# PowerSupply.net
KiCad netlist of a schematic drawn in Altium Designer
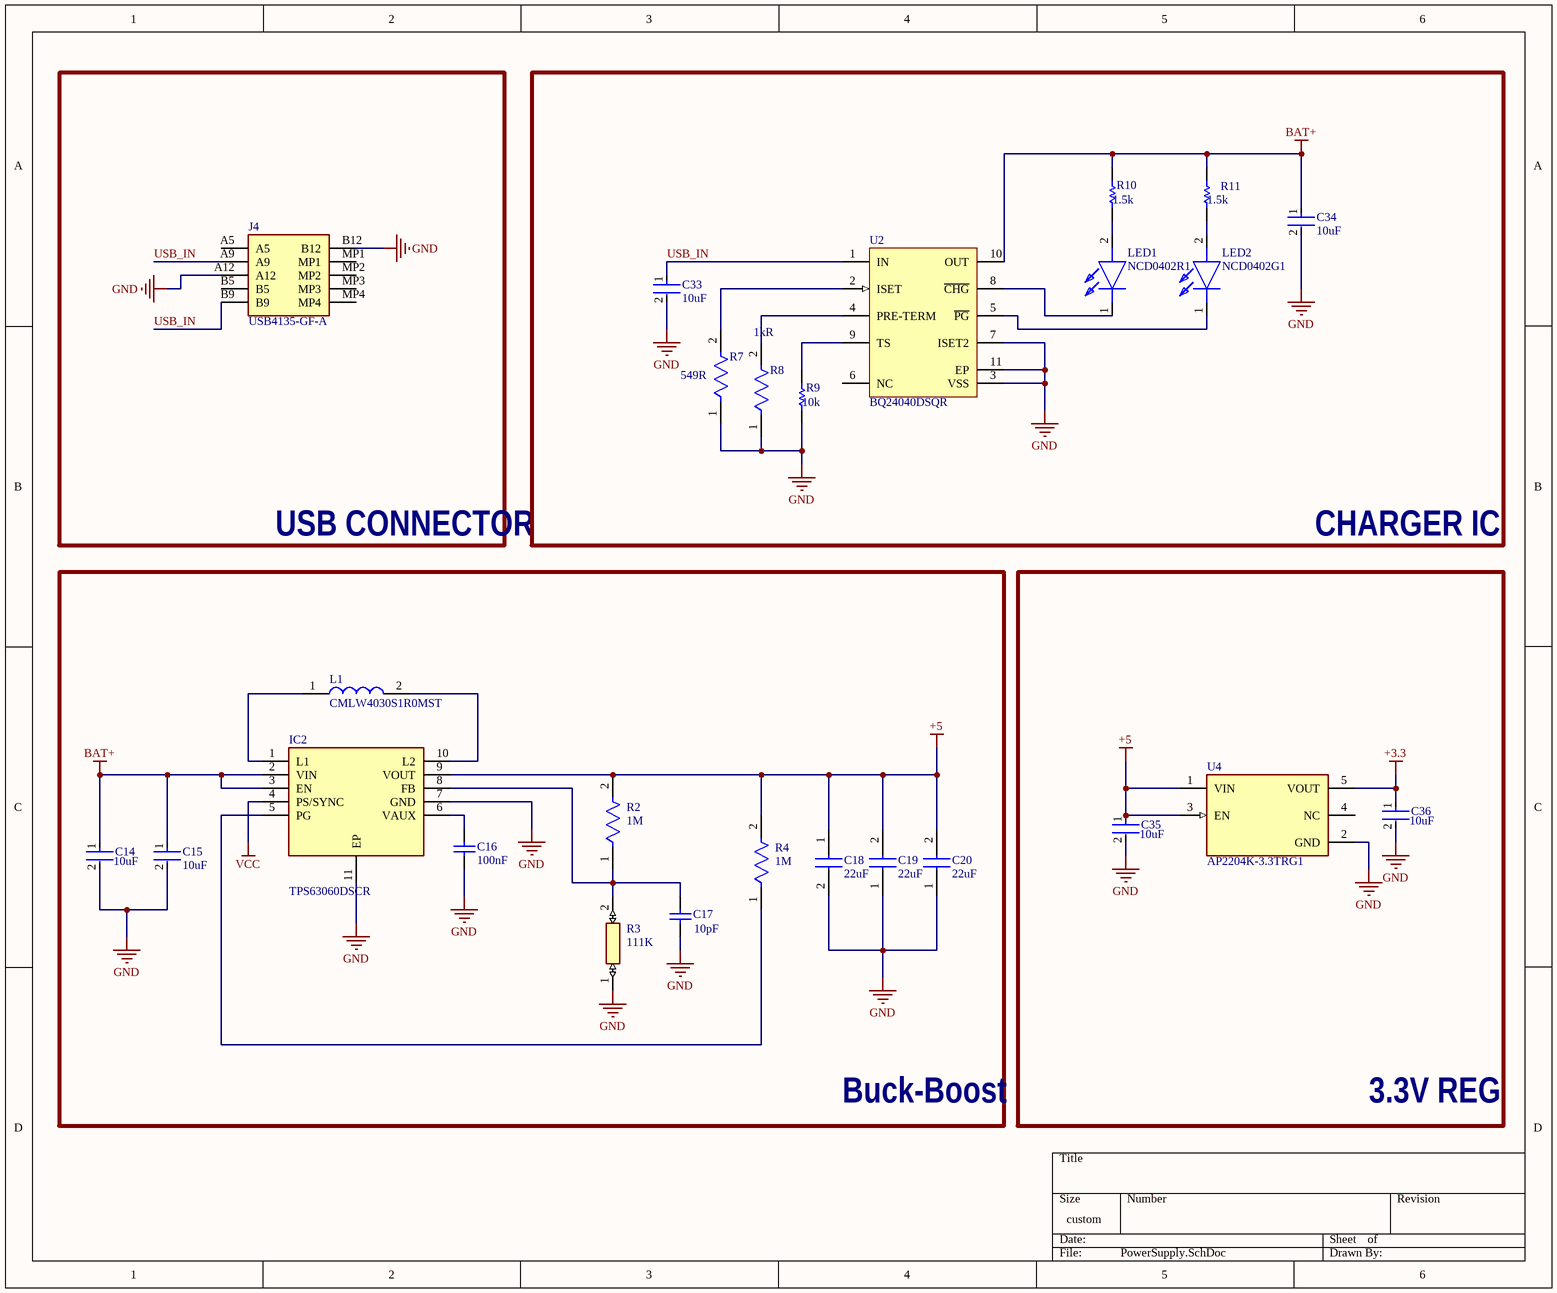
[diagram p0: PowerSupply.SchDoc]

(export (version "E")
  (design (tool "Eeschema 10.0.6"))
  (components
    (comp (ref "C14")
      (value "CL05A106MP5NUNC")
      (footprint "FP-CL05A106MP5NUNC-MFG")
      (description "CAP CER 10UF 10V X5R 0402")
      (fields
        (field (name "OCTOPART") "https://octopart.com/cl05a106mp5nunc-samsung-22457395")
        (field (name "TOLERANCE") "20%")
        (field (name "CAPACITANCE") "10uF")
      )
      (libsource (lib "Altium Content Vault") (part "b4654b650e69147ec39a6b967a45e02"))
    )
    (comp (ref "C15")
      (value "CL05A106MP5NUNC")
      (footprint "FP-CL05A106MP5NUNC-MFG")
      (description "CAP CER 10UF 10V X5R 0402")
      (fields
        (field (name "OCTOPART") "https://octopart.com/cl05a106mp5nunc-samsung-22457395")
        (field (name "TOLERANCE") "20%")
        (field (name "CAPACITANCE") "10uF")
      )
      (libsource (lib "Altium Content Vault") (part "b4654b650e69147ec39a6b967a45e02"))
    )
    (comp (ref "C16")
      (value "CL05B104KO5NNNC")
      (footprint "CAPC1050X55X23ML05T13")
      (description "Chip Capacitor, 100 nF, +/- 10%, 16 V, -55 to 125 degC, 0402 (1005 Metric), RoHS, Tape and Reel")
      (fields (field (name "MANUFACTURER") "Samsung Electro-Mechanics") (field (name "CAPACITANCE") "100nF"))
      (libsource (lib "Altium Content Vault") (part "CAP-NP-2"))
    )
    (comp (ref "C17")
      (value "CC0402JRNPO9BN100")
      (footprint "CAPC1005X55X25ML05T05")
      (description "Chip Capacitor, 10 pF, +/- 5%, 50 V, -55 to 125 degC, 0402 (1005 Metric), RoHS, Tape and Reel")
      (fields
        (field (name "TOLERANCE") "5%")
        (field (name "MANUFACTURER") "Yageo")
        (field (name "CAPACITANCE") "10pF")
      )
      (libsource (lib "Altium Content Vault") (part "CAP-NP-2"))
    )
    (comp (ref "C18")
      (value "22uF")
      (footprint "SamacSys:CAPC1608X105N")
      (description "Capacitor")
      (fields
        (field (name "MANUFACTURER_PART_NUMBER") "CL10A226MP8NUNE")
        (field (name "MOUSER PART NUMBER") "187-CL10A226MP8NUNE")
      )
      (libsource (lib "*") (part "CL10A226MP8NUNE"))
    )
    (comp (ref "C19")
      (value "22uF")
      (footprint "SamacSys:CAPC1608X105N")
      (description "Capacitor")
      (fields
        (field (name "MANUFACTURER_PART_NUMBER") "CL10A226MP8NUNE")
        (field (name "MOUSER PART NUMBER") "187-CL10A226MP8NUNE")
      )
      (libsource (lib "*") (part "CL10A226MP8NUNE"))
    )
    (comp (ref "C20")
      (value "22uF")
      (footprint "SamacSys:CAPC1608X105N")
      (description "Capacitor")
      (fields
        (field (name "MANUFACTURER_PART_NUMBER") "CL10A226MP8NUNE")
        (field (name "MOUSER PART NUMBER") "187-CL10A226MP8NUNE")
      )
      (libsource (lib "*") (part "CL10A226MP8NUNE"))
    )
    (comp (ref "C33")
      (value "CL05A106MP5NUNC")
      (footprint "FP-CL05A106MP5NUNC-MFG")
      (description "CAP CER 10UF 10V X5R 0402")
      (fields
        (field (name "OCTOPART") "https://octopart.com/cl05a106mp5nunc-samsung-22457395")
        (field (name "TOLERANCE") "20%")
        (field (name "CAPACITANCE") "10uF")
      )
      (libsource (lib "Altium Content Vault") (part "b4654b650e69147ec39a6b967a45e02"))
    )
    (comp (ref "C34")
      (value "CL05A106MP5NUNC")
      (footprint "FP-CL05A106MP5NUNC-MFG")
      (description "CAP CER 10UF 10V X5R 0402")
      (fields
        (field (name "OCTOPART") "https://octopart.com/cl05a106mp5nunc-samsung-22457395")
        (field (name "TOLERANCE") "20%")
        (field (name "CAPACITANCE") "10uF")
      )
      (libsource (lib "Altium Content Vault") (part "b4654b650e69147ec39a6b967a45e02"))
    )
    (comp (ref "C35")
      (value "CL05A106MP5NUNC")
      (footprint "FP-CL05A106MP5NUNC-MFG")
      (description "CAP CER 10UF 10V X5R 0402")
      (fields
        (field (name "OCTOPART") "https://octopart.com/cl05a106mp5nunc-samsung-22457395")
        (field (name "TOLERANCE") "20%")
        (field (name "CAPACITANCE") "10uF")
      )
      (libsource (lib "Altium Content Vault") (part "b4654b650e69147ec39a6b967a45e02"))
    )
    (comp (ref "C36")
      (value "CL05A106MP5NUNC")
      (footprint "FP-CL05A106MP5NUNC-MFG")
      (description "CAP CER 10UF 10V X5R 0402")
      (fields
        (field (name "OCTOPART") "https://octopart.com/cl05a106mp5nunc-samsung-22457395")
        (field (name "TOLERANCE") "20%")
        (field (name "CAPACITANCE") "10uF")
      )
      (libsource (lib "Altium Content Vault") (part "b4654b650e69147ec39a6b967a45e02"))
    )
    (comp (ref "IC2")
      (value "TPS63060DSCR")
      (footprint "SamacSys:SON50P300X300X80-11N-D")
      (description "Integrated Circuit")
      (fields (field (name "MOUSER PART NUMBER") "595-TPS63060DSCR"))
      (libsource (lib "*") (part "TPS63060DSCR"))
    )
    (comp (ref "J4")
      (value "USB4135-GF-A")
      (footprint "SamacSys:USB4135GFA")
      (description "Connector")
      (fields (field (name "MOUSER PART NUMBER") "640-USB4135-GF-A"))
      (libsource (lib "SamacSys") (part "USB4135-GF-A"))
    )
    (comp (ref "L1")
      (value "CMLW4030S1R0MST")
      (footprint "SamacSys:LSDPD4040WKT4R7MML")
      (description "Inductor")
      (fields
        (field (name "MANUFACTURER_PART_NUMBER") "LSDPD4040WKT4R7MML")
        (field (name "MOUSER PART NUMBER") "963-LSDPD4040WKT4R7M")
      )
      (libsource (lib "*") (part "LSDPD4040WKT4R7MML"))
    )
    (comp (ref "LED1")
      (value "NCD0402R1")
      (footprint "SamacSys:NCD0402R1")
      (description "LED")
      (libsource (lib "*") (part "NCD0402R1"))
    )
    (comp (ref "LED2")
      (value "NCD0402G1")
      (footprint "SamacSys:NCD0402R1")
      (description "LED  NCD0402G1")
      (fields (field (name "MANUFACTURER_PART_NUMBER") "NCD0402R1"))
      (libsource (lib "*") (part "NCD0402R1"))
    )
    (comp (ref "R2")
      (value "1M")
      (footprint "FP-AC0402-IPC_C")
      (description "RES 1MΩ ±0.5% 0.063W 0402")
      (fields (field (name "Comment") "AC0402DR-071ML"))
      (libsource (lib "Altium Content Vault") (part "1029c3af85768c4190bb7ad29bc67b5"))
    )
    (comp (ref "R3")
      (value "111K")
      (footprint "SamacSys:RESC2012X60N")
      (description "Resistor")
      (fields
        (field (name "MANUFACTURER_PART_NUMBER") "RT0805BRD07111KL")
        (field (name "MOUSER PART NUMBER") "603-RT0805BRD07111KL")
      )
      (libsource (lib "*") (part "RT0805BRD07111KL"))
    )
    (comp (ref "R4")
      (value "1M")
      (footprint "FP-AC0402-IPC_C")
      (description "RES 1MΩ ±0.5% 0.063W 0402")
      (fields (field (name "Comment") "AC0402DR-071ML"))
      (libsource (lib "Altium Content Vault") (part "1029c3af85768c4190bb7ad29bc67b5"))
    )
    (comp (ref "R7")
      (value "AC0402FR-07549RL")
      (footprint "FP-AC0402-IPC_B")
      (description "RES 549Ω ±1% 0.063W 0402")
      (fields (field (name "TOLERANCE") "1%") (field (name "RESISTANCE") "549R"))
      (libsource (lib "Altium Content Vault") (part "1029c3af85768c4190bb7ad29bc67b5"))
    )
    (comp (ref "R8")
      (value "RC0402FR-071KL")
      (footprint "FP-RC0402-0_4-IPC_A")
      (description "RES 1K OHM 1% 1/16W 0402")
      (fields (field (name "TOLERANCE") "1%") (field (name "RESISTANCE") "1kR"))
      (libsource (lib "Altium Content Vault") (part "1029c3af85768c4190bb7ad29bc67b5"))
    )
    (comp (ref "R9")
      (value "10k")
      (footprint "RESC1005X40X25ML05T10")
      (fields (field (name "PART NUMBER") "RC0402FR-0710KL") (field (name "MANUFACTURER") "Yageo / Phycomp"))
      (libsource (lib "Altium Content Vault") (part "RES"))
    )
    (comp (ref "R10")
      (value "1.5k")
      (footprint "RESC1005X40X25ML05T10")
      (fields (field (name "MANUFACTURER") "Yageo / Phycomp") (field (name "PART NUMBER") "RC0402FR-071K5L"))
      (libsource (lib "Altium Content Vault") (part "RES"))
    )
    (comp (ref "R11")
      (value "1.5k")
      (footprint "RESC1005X40X25ML05T10")
      (fields (field (name "MANUFACTURER") "Yageo / Phycomp") (field (name "PART NUMBER") "RC0402FR-071K5L"))
      (libsource (lib "Altium Content Vault") (part "RES"))
    )
    (comp (ref "U2")
      (value "BQ24040DSQR")
      (footprint "DSQ0010A_V")
      (fields (field (name "MANUFACTURER") "Texas Instruments"))
      (libsource (lib "Altium Content Vault") (part "TI-BQ24040DSQ10-1500X900TP"))
    )
    (comp (ref "U4")
      (value "AP2204K-3.3TRG1")
      (footprint "FP-SOT25-IPC_C")
      (description "IC REG LINEAR 3.3V 150MA SOT23-5")
      (libsource (lib "Altium Content Vault") (part "038a824adfd04a965d73cdd9fb88cf2"))
    )
  )
  (nets
    (net (code "1") (name "+3.3") (class "Default")
      (node (ref "C36") (pin "1") (pinfunction "1_1") (pintype "passive"))
      (node (ref "U4") (pin "5") (pinfunction "VOUT_5") (pintype "power_in"))
    )
    (net (code "2") (name "+5") (class "Default")
      (node (ref "C18") (pin "1") (pinfunction "1_1") (pintype "passive"))
      (node (ref "C19") (pin "2") (pinfunction "2_2") (pintype "passive"))
      (node (ref "C20") (pin "2") (pinfunction "2_2") (pintype "passive"))
      (node (ref "C35") (pin "1") (pinfunction "1_1") (pintype "passive"))
      (node (ref "IC2") (pin "9") (pinfunction "VOUT_9") (pintype "passive"))
      (node (ref "R2") (pin "2") (pinfunction "2_2") (pintype "passive"))
      (node (ref "R4") (pin "2") (pinfunction "2_2") (pintype "passive"))
      (node (ref "U4") (pin "1") (pinfunction "VIN_1") (pintype "power_in"))
      (node (ref "U4") (pin "3") (pinfunction "EN_3") (pintype "input"))
    )
    (net (code "3") (name "/USB_IN") (class "Default")
      (node (ref "C33") (pin "1") (pinfunction "1_1") (pintype "passive"))
      (node (ref "J4") (pin "A9") (pinfunction "A9_A9") (pintype "passive"))
      (node (ref "J4") (pin "B9") (pinfunction "B9_B9") (pintype "passive"))
      (node (ref "U2") (pin "1") (pinfunction "IN_1") (pintype "power_in"))
    )
    (net (code "4") (name "BAT+") (class "Default")
      (node (ref "C14") (pin "1") (pinfunction "1_1") (pintype "passive"))
      (node (ref "C15") (pin "1") (pinfunction "1_1") (pintype "passive"))
      (node (ref "C34") (pin "1") (pinfunction "1_1") (pintype "passive"))
      (node (ref "IC2") (pin "2") (pinfunction "VIN_2") (pintype "passive"))
      (node (ref "IC2") (pin "3") (pinfunction "EN_3") (pintype "passive"))
      (node (ref "R10") (pin "2") (pinfunction "2_2") (pintype "passive"))
      (node (ref "R11") (pin "2") (pinfunction "2_2") (pintype "passive"))
      (node (ref "U2") (pin "10") (pinfunction "OUT_10") (pintype "power_in"))
    )
    (net (code "5") (name "GND") (class "Default")
      (node (ref "C14") (pin "2") (pinfunction "2_2") (pintype "passive"))
      (node (ref "C15") (pin "2") (pinfunction "2_2") (pintype "passive"))
      (node (ref "C16") (pin "1") (pinfunction "1_1") (pintype "passive"))
      (node (ref "C17") (pin "1") (pinfunction "1_1") (pintype "passive"))
      (node (ref "C18") (pin "2") (pinfunction "2_2") (pintype "passive"))
      (node (ref "C19") (pin "1") (pinfunction "1_1") (pintype "passive"))
      (node (ref "C20") (pin "1") (pinfunction "1_1") (pintype "passive"))
      (node (ref "C33") (pin "2") (pinfunction "2_2") (pintype "passive"))
      (node (ref "C34") (pin "2") (pinfunction "2_2") (pintype "passive"))
      (node (ref "C35") (pin "2") (pinfunction "2_2") (pintype "passive"))
      (node (ref "C36") (pin "2") (pinfunction "2_2") (pintype "passive"))
      (node (ref "IC2") (pin "11") (pinfunction "EP_11") (pintype "passive"))
      (node (ref "IC2") (pin "7") (pinfunction "GND_7") (pintype "passive"))
      (node (ref "J4") (pin "A12") (pinfunction "A12_A12") (pintype "passive"))
      (node (ref "J4") (pin "B12") (pinfunction "B12_B12") (pintype "passive"))
      (node (ref "R3") (pin "1") (pinfunction "1_1") (pintype "bidirectional"))
      (node (ref "R7") (pin "1") (pinfunction "1_1") (pintype "passive"))
      (node (ref "R8") (pin "1") (pinfunction "1_1") (pintype "passive"))
      (node (ref "R9") (pin "1") (pinfunction "1_1") (pintype "passive"))
      (node (ref "U2") (pin "11") (pinfunction "EP_11") (pintype "power_in"))
      (node (ref "U2") (pin "3") (pinfunction "VSS_3") (pintype "power_in"))
      (node (ref "U2") (pin "7") (pinfunction "ISET2_7") (pintype "passive"))
      (node (ref "U4") (pin "2") (pinfunction "GND_2") (pintype "power_in"))
    )
    (net (code "6") (name "Net-(IC2-FB)") (class "Default")
      (node (ref "C17") (pin "2") (pinfunction "2_2") (pintype "passive"))
      (node (ref "IC2") (pin "8") (pinfunction "FB_8") (pintype "passive"))
      (node (ref "R2") (pin "1") (pinfunction "1_1") (pintype "passive"))
      (node (ref "R3") (pin "2") (pinfunction "2_2") (pintype "bidirectional"))
    )
    (net (code "7") (name "Net-(IC2-L1)") (class "Default")
      (node (ref "IC2") (pin "1") (pinfunction "L1_1") (pintype "passive"))
      (node (ref "L1") (pin "1") (pinfunction "1_1") (pintype "passive"))
    )
    (net (code "8") (name "Net-(IC2-L2)") (class "Default")
      (node (ref "IC2") (pin "10") (pinfunction "L2_10") (pintype "passive"))
      (node (ref "L1") (pin "2") (pinfunction "2_2") (pintype "passive"))
    )
    (net (code "9") (name "Net-(IC2-PG)") (class "Default")
      (node (ref "IC2") (pin "5") (pinfunction "PG_5") (pintype "passive"))
      (node (ref "R4") (pin "1") (pinfunction "1_1") (pintype "passive"))
    )
    (net (code "10") (name "Net-(IC2-VAUX)") (class "Default")
      (node (ref "C16") (pin "2") (pinfunction "2_2") (pintype "passive"))
      (node (ref "IC2") (pin "6") (pinfunction "VAUX_6") (pintype "passive"))
    )
    (net (code "11") (name "Net-(LED1-A)") (class "Default")
      (node (ref "LED1") (pin "2") (pinfunction "A_2") (pintype "passive"))
      (node (ref "R10") (pin "1") (pinfunction "1_1") (pintype "passive"))
    )
    (net (code "12") (name "Net-(LED1-K)") (class "Default")
      (node (ref "LED1") (pin "1") (pinfunction "K_1") (pintype "passive"))
      (node (ref "U2") (pin "8") (pinfunction "~{CHG}_8") (pintype "tri_state"))
    )
    (net (code "13") (name "Net-(LED2-A)") (class "Default")
      (node (ref "LED2") (pin "2") (pinfunction "A_2") (pintype "passive"))
      (node (ref "R11") (pin "1") (pinfunction "1_1") (pintype "passive"))
    )
    (net (code "14") (name "Net-(LED2-K)") (class "Default")
      (node (ref "LED2") (pin "1") (pinfunction "K_1") (pintype "passive"))
      (node (ref "U2") (pin "5") (pinfunction "~{PG}_5") (pintype "tri_state"))
    )
    (net (code "15") (name "Net-(U2-ISET)") (class "Default")
      (node (ref "R7") (pin "2") (pinfunction "2_2") (pintype "passive"))
      (node (ref "U2") (pin "2") (pinfunction "ISET_2") (pintype "input"))
    )
    (net (code "16") (name "Net-(U2-PRE-TERM)") (class "Default")
      (node (ref "R8") (pin "2") (pinfunction "2_2") (pintype "passive"))
      (node (ref "U2") (pin "4") (pinfunction "PRE-TERM_4") (pintype "passive"))
    )
    (net (code "17") (name "Net-(U2-TS)") (class "Default")
      (node (ref "R9") (pin "2") (pinfunction "2_2") (pintype "passive"))
      (node (ref "U2") (pin "9") (pinfunction "TS_9") (pintype "passive"))
    )
    (net (code "18") (name "VCC") (class "Default")
      (node (ref "IC2") (pin "4") (pinfunction "PS/SYNC_4") (pintype "passive"))
    )
    (net (code "19") (name "unconnected-(J4-PadA5)") (class "Default")
      (node (ref "J4") (pin "A5") (pinfunction "A5_A5") (pintype "passive"))
    )
    (net (code "20") (name "unconnected-(J4-PadB5)") (class "Default")
      (node (ref "J4") (pin "B5") (pinfunction "B5_B5") (pintype "passive"))
    )
    (net (code "21") (name "unconnected-(J4-PadMP1)") (class "Default")
      (node (ref "J4") (pin "MP1") (pinfunction "MP1_MP1") (pintype "passive"))
    )
    (net (code "22") (name "unconnected-(J4-PadMP2)") (class "Default")
      (node (ref "J4") (pin "MP2") (pinfunction "MP2_MP2") (pintype "passive"))
    )
    (net (code "23") (name "unconnected-(J4-PadMP3)") (class "Default")
      (node (ref "J4") (pin "MP3") (pinfunction "MP3_MP3") (pintype "passive"))
    )
    (net (code "24") (name "unconnected-(J4-PadMP4)") (class "Default")
      (node (ref "J4") (pin "MP4") (pinfunction "MP4_MP4") (pintype "passive"))
    )
    (net (code "25") (name "unconnected-(U2-NC-Pad6)") (class "Default")
      (node (ref "U2") (pin "6") (pinfunction "NC_6") (pintype "passive"))
    )
    (net (code "26") (name "unconnected-(U4-NC-Pad4)") (class "Default")
      (node (ref "U4") (pin "4") (pinfunction "NC_4") (pintype "passive"))
    )
  )
)
